# amp-LO-QPA4463A.net
KiCad netlist of a schematic drawn in EAGLE
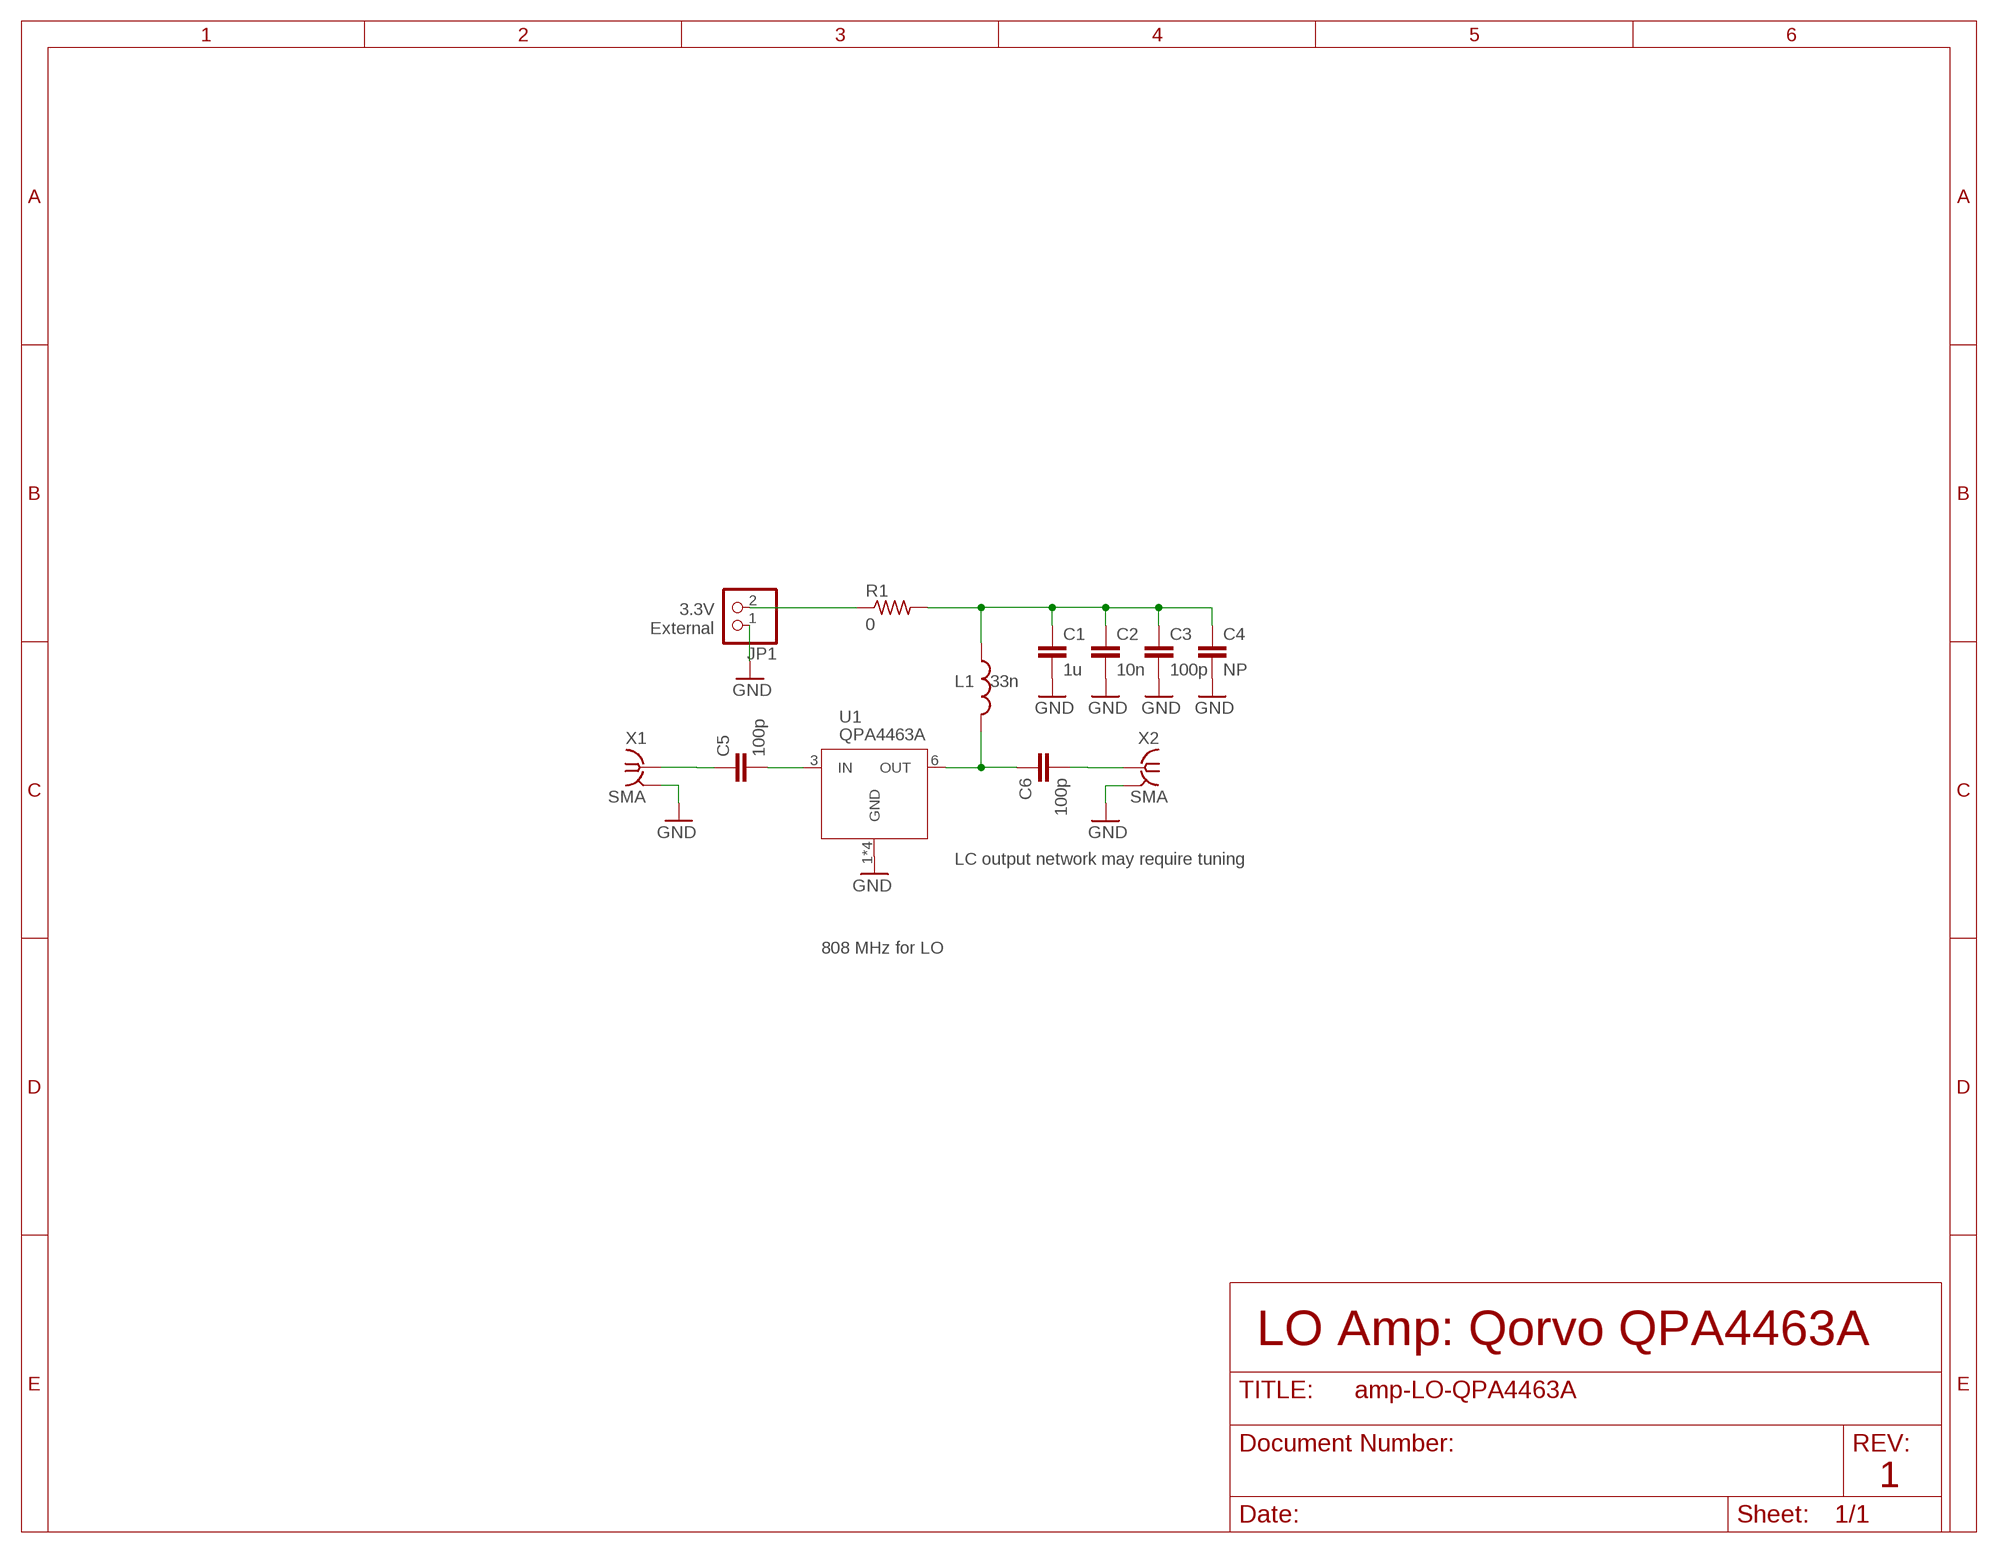
[diagram p0: schematic, sheet 1]

(export (version "E")
  (design (tool "Eeschema 10.0.6"))
  (components
    (comp (ref "C1")
      (value "1u")
      (footprint "eagle-import:.0603-B-NOSILK")
      (libsource (lib "eagle-import") (part "C-EU0603-B-NOSILK"))
    )
    (comp (ref "C2")
      (value "10n")
      (footprint "eagle-import:.0603-B-NOSILK")
      (libsource (lib "eagle-import") (part "C-EU0603-B-NOSILK"))
    )
    (comp (ref "C3")
      (value "100p")
      (footprint "eagle-import:.0603-B-NOSILK")
      (libsource (lib "eagle-import") (part "C-EU0603-B-NOSILK"))
    )
    (comp (ref "C4")
      (value "NP")
      (footprint "eagle-import:.0603-B-NOSILK")
      (libsource (lib "eagle-import") (part "C-EU0603-B-NOSILK"))
    )
    (comp (ref "C5")
      (value "100p")
      (footprint "eagle-import:.0603-B-NOSILK")
      (libsource (lib "eagle-import") (part "C-EU0603-B-NOSILK"))
    )
    (comp (ref "C6")
      (value "100p")
      (footprint "eagle-import:.0603-B-NOSILK")
      (libsource (lib "eagle-import") (part "C-EU0603-B-NOSILK"))
    )
    (comp (ref "JP1")
      (value "PINHD-1X2")
      (footprint "eagle-import:1X02")
      (libsource (lib "eagle-import") (part "PINHD-1X2"))
    )
    (comp (ref "L1")
      (value "33n")
      (footprint "eagle-import:.0805-B-NOSILK")
      (libsource (lib "eagle-import") (part "L-US0805-B-NOSILK"))
    )
    (comp (ref "R1")
      (value "0")
      (footprint "eagle-import:.0805-B-NOSILK")
      (libsource (lib "eagle-import") (part "R-US_0805-B-NOSILK"))
    )
    (comp (ref "U1")
      (value "QPA4463A")
      (footprint "eagle-import:SOT363")
      (libsource (lib "eagle-import") (part "QPA4463A"))
    )
    (comp (ref "X1")
      (value "SMA")
      (footprint "eagle-import:J502-ND-142-0701-801_806")
      (fields (field (name "MF") "JOHNSON COMPONENTS") (field (name "MPN") "142-0701-801"))
      (libsource (lib "eagle-import") (part "SMA-142-0701-801/806"))
    )
    (comp (ref "X2")
      (value "SMA")
      (footprint "eagle-import:J502-ND-142-0701-801_806")
      (fields (field (name "MF") "JOHNSON COMPONENTS") (field (name "MPN") "142-0701-801"))
      (libsource (lib "eagle-import") (part "SMA-142-0701-801/806"))
    )
  )
  (nets
    (net (code "1") (name "GND") (class "Default")
      (node (ref "C1") (pin "2") (pinfunction "2_2") (pintype "passive"))
      (node (ref "C2") (pin "2") (pinfunction "2_2") (pintype "passive"))
      (node (ref "C3") (pin "2") (pinfunction "2_2") (pintype "passive"))
      (node (ref "C4") (pin "2") (pinfunction "2_2") (pintype "passive"))
      (node (ref "JP1") (pin "1") (pinfunction "1_1") (pintype "passive"))
      (node (ref "U1") (pin "1") (pinfunction "GND_1") (pintype "power_in"))
      (node (ref "U1") (pin "2") (pinfunction "GND_2") (pintype "power_in"))
      (node (ref "U1") (pin "4") (pinfunction "GND_4") (pintype "power_in"))
      (node (ref "U1") (pin "5") (pinfunction "GND_5") (pintype "power_in"))
      (node (ref "X1") (pin "G@1") (pinfunction "2_G@1") (pintype "passive"))
      (node (ref "X1") (pin "G@2") (pinfunction "2_G@2") (pintype "passive"))
      (node (ref "X1") (pin "G@3") (pinfunction "2_G@3") (pintype "passive"))
      (node (ref "X1") (pin "G@4") (pinfunction "2_G@4") (pintype "passive"))
      (node (ref "X2") (pin "G@1") (pinfunction "2_G@1") (pintype "passive"))
      (node (ref "X2") (pin "G@2") (pinfunction "2_G@2") (pintype "passive"))
      (node (ref "X2") (pin "G@3") (pinfunction "2_G@3") (pintype "passive"))
      (node (ref "X2") (pin "G@4") (pinfunction "2_G@4") (pintype "passive"))
    )
    (net (code "2") (name "Net-(C1-Pad1)") (class "Default")
      (node (ref "C1") (pin "1") (pinfunction "1_1") (pintype "passive"))
      (node (ref "C2") (pin "1") (pinfunction "1_1") (pintype "passive"))
      (node (ref "C3") (pin "1") (pinfunction "1_1") (pintype "passive"))
      (node (ref "C4") (pin "1") (pinfunction "1_1") (pintype "passive"))
      (node (ref "L1") (pin "1") (pinfunction "1_1") (pintype "passive"))
      (node (ref "R1") (pin "2") (pinfunction "2_2") (pintype "passive"))
    )
    (net (code "3") (name "Net-(C5-Pad1)") (class "Default")
      (node (ref "C5") (pin "1") (pinfunction "1_1") (pintype "passive"))
      (node (ref "X1") (pin "1") (pinfunction "1_1") (pintype "passive"))
    )
    (net (code "4") (name "Net-(C6-Pad2)") (class "Default")
      (node (ref "C6") (pin "2") (pinfunction "2_2") (pintype "passive"))
      (node (ref "X2") (pin "1") (pinfunction "1_1") (pintype "passive"))
    )
    (net (code "5") (name "Net-(JP1-Pad2)") (class "Default")
      (node (ref "JP1") (pin "2") (pinfunction "2_2") (pintype "passive"))
      (node (ref "R1") (pin "1") (pinfunction "1_1") (pintype "passive"))
    )
    (net (code "6") (name "Net-(U1-IN)") (class "Default")
      (node (ref "C5") (pin "2") (pinfunction "2_2") (pintype "passive"))
      (node (ref "U1") (pin "3") (pinfunction "IN_3") (pintype "input"))
    )
    (net (code "7") (name "Net-(U1-OUT)") (class "Default")
      (node (ref "C6") (pin "1") (pinfunction "1_1") (pintype "passive"))
      (node (ref "L1") (pin "2") (pinfunction "2_2") (pintype "passive"))
      (node (ref "U1") (pin "6") (pinfunction "OUT_6") (pintype "output"))
    )
  )
)
